# PiHAT_SSR_V4.net
KiCad netlist of a schematic drawn in EAGLE
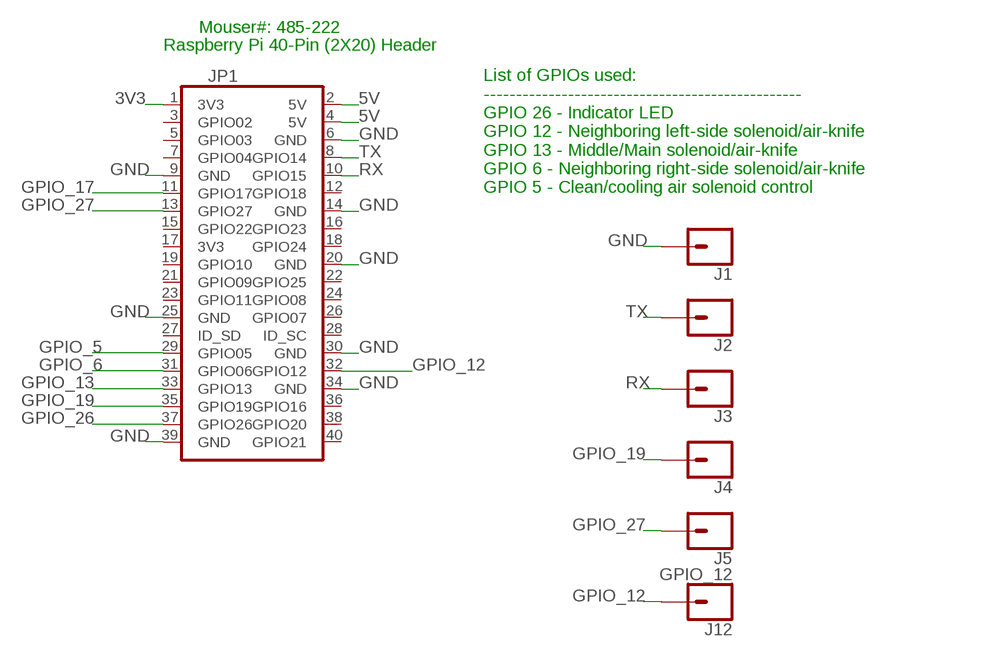
[diagram p0: schematic, sheet 1]
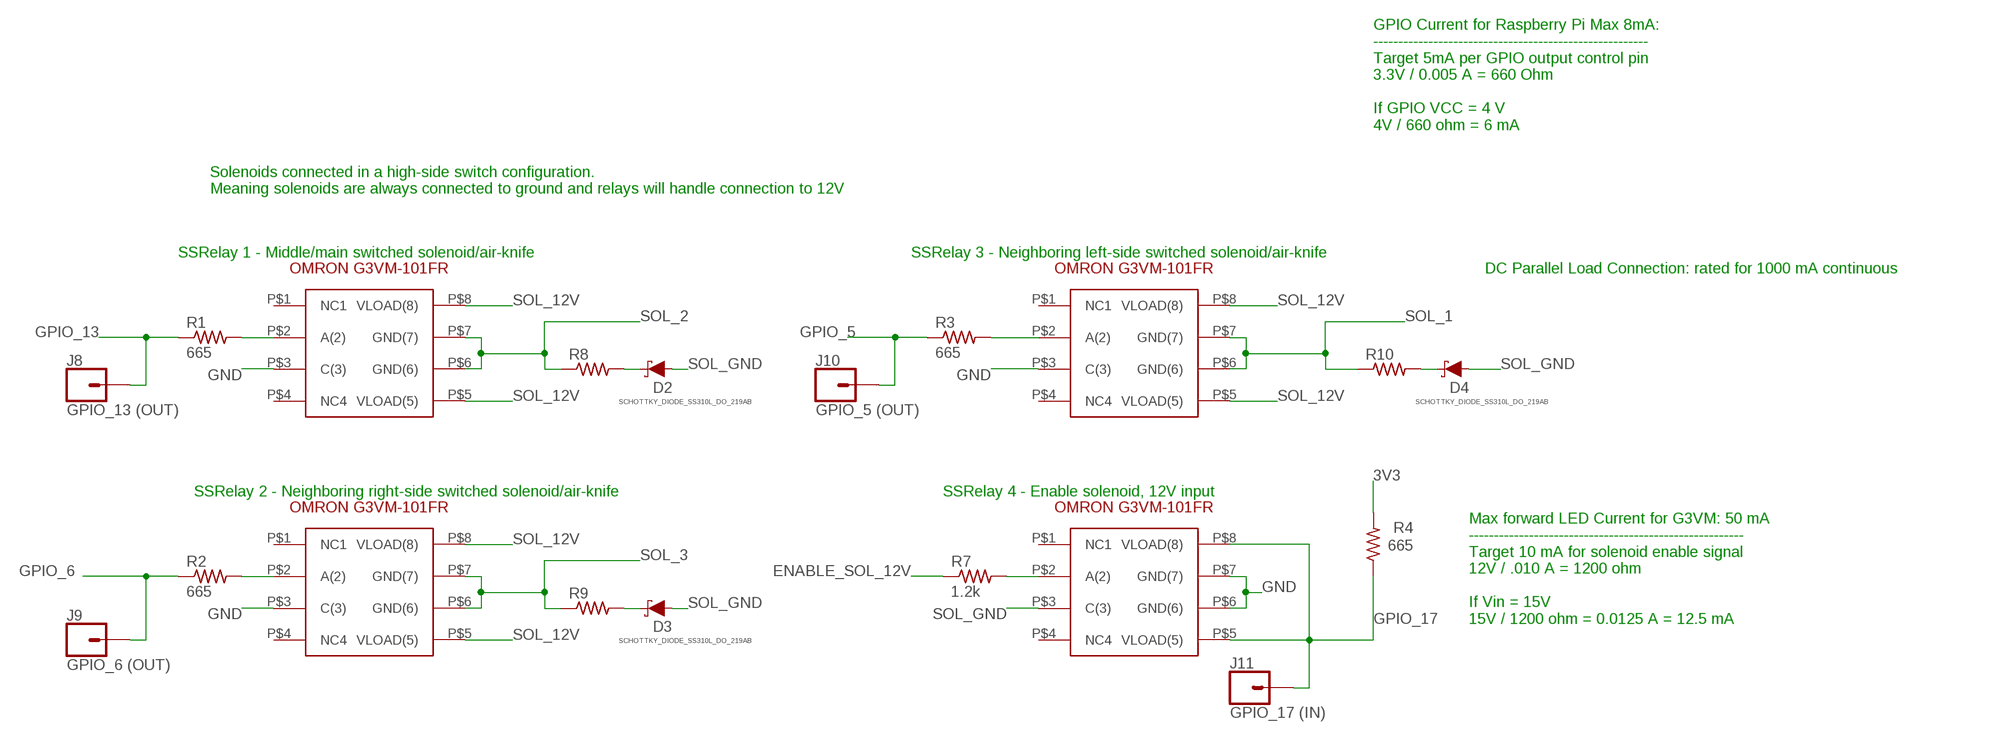
[diagram p1: schematic, sheet 2]
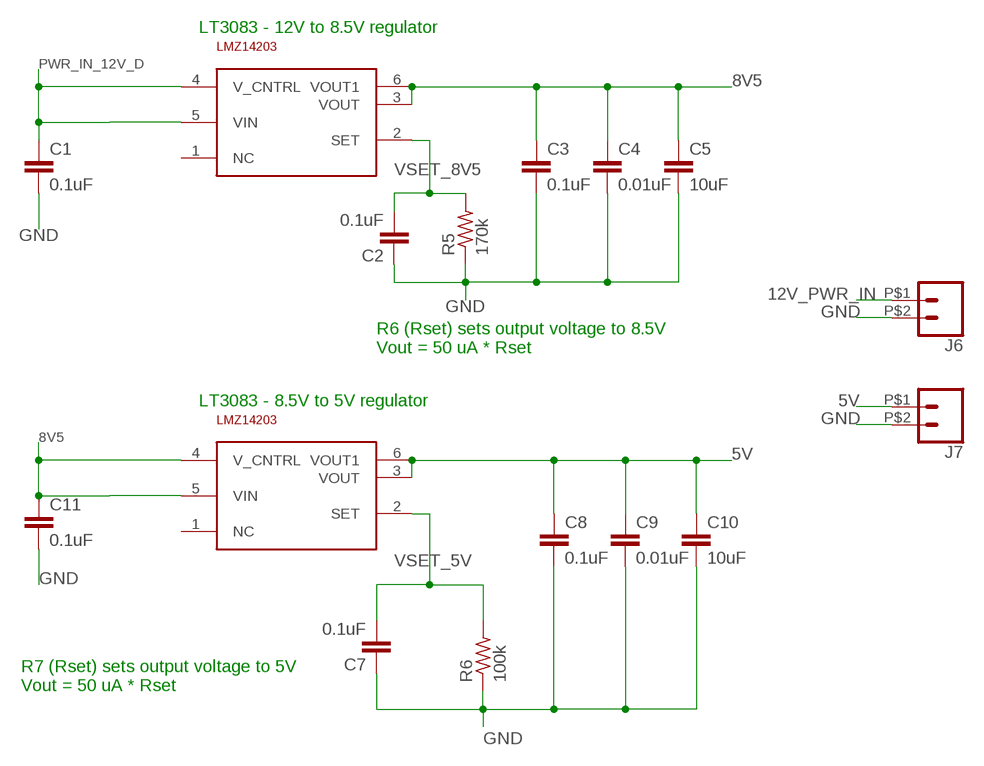
[diagram p2: schematic, sheet 3]
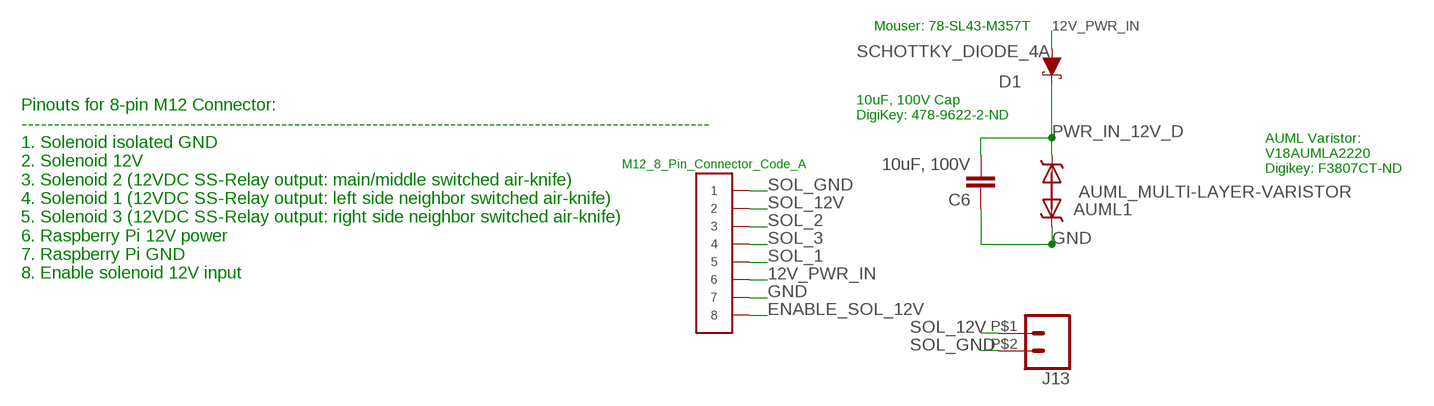
[diagram p3: schematic, sheet 4]

(export (version "E")
  (design (tool "Eeschema 10.0.6"))
  (components
    (comp (ref "AUML1")
      (value "SMD-SPECIAL_28PIN_PIC32_11_3_2011_MOD5_20_13_AUML_MULTI-LAYER-VARISTOR")
      (footprint "eagle-import:SMD-SPECIAL_28PIN_PIC32_11_3_2011_MOD5_20_13_SMT_CAP_2220")
      (libsource (lib "eagle-import") (part "SMD-SPECIAL_28PIN_PIC32_11_3_2011_MOD5_20_13_AUML_MULTI-LAYER-VARISTOR"))
    )
    (comp (ref "C6")
      (value "10uF, 100V")
      (footprint "eagle-import:C2220K")
      (libsource (lib "eagle-import") (part "C-EUC2220K"))
    )
    (comp (ref "CN1")
      (value "M12_8PIN_CODE_A")
      (footprint "eagle-import:M12_8PIN_CODE_A")
      (libsource (lib "eagle-import") (part "M12_8PIN_CODE_A"))
    )
    (comp (ref "D1")
      (value "SCHOTTKY_DIODE_4A")
      (footprint "eagle-import:SCHOTTKY_DIODE_SMD_DO-214AB")
      (libsource (lib "eagle-import") (part "SCHOTTKY_DIODE_4A"))
    )
    (comp (ref "J13")
      (value "CONN_02PTH2")
      (footprint "eagle-import:1X02_BIG")
      (libsource (lib "eagle-import") (part "CONN_02PTH2"))
    )
    (comp (ref "D2")
      (value "SCHOTTKY_DIODE_SS310L_DO_219AB")
      (footprint "eagle-import:SCHOTTKY_DIODE_DO219AB")
      (libsource (lib "eagle-import") (part "SCHOTTKY_DIODE_SS310L_DO_219AB"))
    )
    (comp (ref "D3")
      (value "SCHOTTKY_DIODE_SS310L_DO_219AB")
      (footprint "eagle-import:SCHOTTKY_DIODE_DO219AB")
      (libsource (lib "eagle-import") (part "SCHOTTKY_DIODE_SS310L_DO_219AB"))
    )
    (comp (ref "D4")
      (value "SCHOTTKY_DIODE_SS310L_DO_219AB")
      (footprint "eagle-import:SCHOTTKY_DIODE_DO219AB")
      (libsource (lib "eagle-import") (part "SCHOTTKY_DIODE_SS310L_DO_219AB"))
    )
    (comp (ref "J8")
      (value "GPIO_13 (OUT)")
      (footprint "eagle-import:1X01")
      (libsource (lib "eagle-import") (part "CONN_01"))
    )
    (comp (ref "J9")
      (value "GPIO_6 (OUT)")
      (footprint "eagle-import:1X01")
      (libsource (lib "eagle-import") (part "CONN_01"))
    )
    (comp (ref "J10")
      (value "GPIO_5 (OUT)")
      (footprint "eagle-import:1X01")
      (libsource (lib "eagle-import") (part "CONN_01"))
    )
    (comp (ref "J11")
      (value "GPIO_17 (IN)")
      (footprint "eagle-import:1X01")
      (libsource (lib "eagle-import") (part "CONN_01"))
    )
    (comp (ref "R1")
      (value "665")
      (footprint "eagle-import:M0805")
      (libsource (lib "eagle-import") (part "R-US_M0805"))
    )
    (comp (ref "R2")
      (value "665")
      (footprint "eagle-import:M0805")
      (libsource (lib "eagle-import") (part "R-US_M0805"))
    )
    (comp (ref "R3")
      (value "665")
      (footprint "eagle-import:M0805")
      (libsource (lib "eagle-import") (part "R-US_M0805"))
    )
    (comp (ref "R4")
      (value "665")
      (footprint "eagle-import:M0805")
      (libsource (lib "eagle-import") (part "R-US_M0805"))
    )
    (comp (ref "R7")
      (value "1.2k")
      (footprint "eagle-import:M0805")
      (libsource (lib "eagle-import") (part "R-US_M0805"))
    )
    (comp (ref "R8")
      (value "R-US_R2512")
      (footprint "eagle-import:R2512")
      (libsource (lib "eagle-import") (part "R-US_R2512"))
    )
    (comp (ref "R9")
      (value "R-US_R2512")
      (footprint "eagle-import:R2512")
      (libsource (lib "eagle-import") (part "R-US_R2512"))
    )
    (comp (ref "R10")
      (value "R-US_R2512")
      (footprint "eagle-import:R2512")
      (libsource (lib "eagle-import") (part "R-US_R2512"))
    )
    (comp (ref "SSR1")
      (value "OMRON_G3VM_101FR")
      (footprint "eagle-import:OMRON_G3VM-101FR")
      (libsource (lib "eagle-import") (part "OMRON_G3VM_101FR"))
    )
    (comp (ref "SSR2")
      (value "OMRON_G3VM_101FR")
      (footprint "eagle-import:OMRON_G3VM-101FR")
      (libsource (lib "eagle-import") (part "OMRON_G3VM_101FR"))
    )
    (comp (ref "SSR3")
      (value "OMRON_G3VM_101FR")
      (footprint "eagle-import:OMRON_G3VM-101FR")
      (libsource (lib "eagle-import") (part "OMRON_G3VM_101FR"))
    )
    (comp (ref "SSR4")
      (value "OMRON_G3VM_101FR")
      (footprint "eagle-import:OMRON_G3VM-101FR")
      (libsource (lib "eagle-import") (part "OMRON_G3VM_101FR"))
    )
    (comp (ref "J1")
      (value "CONN_01")
      (footprint "eagle-import:1X01")
      (libsource (lib "eagle-import") (part "CONN_01"))
    )
    (comp (ref "J2")
      (value "CONN_01")
      (footprint "eagle-import:1X01")
      (libsource (lib "eagle-import") (part "CONN_01"))
    )
    (comp (ref "J3")
      (value "CONN_01")
      (footprint "eagle-import:1X01")
      (libsource (lib "eagle-import") (part "CONN_01"))
    )
    (comp (ref "J4")
      (value "CONN_01")
      (footprint "eagle-import:1X01")
      (libsource (lib "eagle-import") (part "CONN_01"))
    )
    (comp (ref "J5")
      (value "CONN_01")
      (footprint "eagle-import:1X01")
      (libsource (lib "eagle-import") (part "CONN_01"))
    )
    (comp (ref "J12")
      (value "GPIO_12")
      (footprint "eagle-import:1X01")
      (libsource (lib "eagle-import") (part "CONN_01"))
    )
    (comp (ref "JP1")
      (value "40W_PI_HAT_TPH")
      (footprint "eagle-import:2X20")
      (libsource (lib "eagle-import") (part "40W_PI_HAT_TPH"))
    )
    (comp (ref "C1")
      (value "0.1uF")
      (footprint "eagle-import:C0805")
      (libsource (lib "eagle-import") (part "C-EUC0805"))
    )
    (comp (ref "C2")
      (value "0.1uF")
      (footprint "eagle-import:C0805")
      (libsource (lib "eagle-import") (part "C-EUC0805"))
    )
    (comp (ref "C3")
      (value "0.1uF")
      (footprint "eagle-import:C0805")
      (libsource (lib "eagle-import") (part "C-EUC0805"))
    )
    (comp (ref "C4")
      (value "0.01uF")
      (footprint "eagle-import:C0805")
      (libsource (lib "eagle-import") (part "C-EUC0805"))
    )
    (comp (ref "C5")
      (value "10uF")
      (footprint "eagle-import:C0805")
      (libsource (lib "eagle-import") (part "C-EUC0805"))
    )
    (comp (ref "C7")
      (value "0.1uF")
      (footprint "eagle-import:C0805")
      (libsource (lib "eagle-import") (part "C-EUC0805"))
    )
    (comp (ref "C8")
      (value "0.1uF")
      (footprint "eagle-import:C0805")
      (libsource (lib "eagle-import") (part "C-EUC0805"))
    )
    (comp (ref "C9")
      (value "0.01uF")
      (footprint "eagle-import:C0805")
      (libsource (lib "eagle-import") (part "C-EUC0805"))
    )
    (comp (ref "C10")
      (value "10uF")
      (footprint "eagle-import:C0805")
      (libsource (lib "eagle-import") (part "C-EUC0805"))
    )
    (comp (ref "C11")
      (value "0.1uF")
      (footprint "eagle-import:C0805")
      (libsource (lib "eagle-import") (part "C-EUC0805"))
    )
    (comp (ref "J6")
      (value "CONN_02PTH2")
      (footprint "eagle-import:1X02_BIG")
      (libsource (lib "eagle-import") (part "CONN_02PTH2"))
    )
    (comp (ref "J7")
      (value "CONN_02PTH2")
      (footprint "eagle-import:1X02_BIG")
      (libsource (lib "eagle-import") (part "CONN_02PTH2"))
    )
    (comp (ref "R5")
      (value "170k")
      (footprint "eagle-import:M0805")
      (libsource (lib "eagle-import") (part "R-US_M0805"))
    )
    (comp (ref "R6")
      (value "100k")
      (footprint "eagle-import:M0805")
      (libsource (lib "eagle-import") (part "R-US_M0805"))
    )
    (comp (ref "VR1")
      (value "SMD-SPECIAL_28PIN_PIC32_11_3_2011_LT3083")
      (footprint "eagle-import:SMD-SPECIAL_28PIN_PIC32_11_3_2011_DPAK-5")
      (libsource (lib "eagle-import") (part "SMD-SPECIAL_28PIN_PIC32_11_3_2011_LT3083"))
    )
    (comp (ref "VR2")
      (value "SMD-SPECIAL_28PIN_PIC32_11_3_2011_LT3083")
      (footprint "eagle-import:SMD-SPECIAL_28PIN_PIC32_11_3_2011_DPAK-5")
      (libsource (lib "eagle-import") (part "SMD-SPECIAL_28PIN_PIC32_11_3_2011_LT3083"))
    )
  )
  (nets
    (net (code "1") (name "3V3") (class "Default")
      (node (ref "JP1") (pin "1") (pinfunction "3V3_1") (pintype "passive"))
      (node (ref "R4") (pin "2") (pinfunction "2_2") (pintype "passive"))
    )
    (net (code "2") (name "5V") (class "Default")
      (node (ref "C10") (pin "1") (pinfunction "1_1") (pintype "passive"))
      (node (ref "C8") (pin "1") (pinfunction "1_1") (pintype "passive"))
      (node (ref "C9") (pin "1") (pinfunction "1_1") (pintype "passive"))
      (node (ref "J7") (pin "P$1") (pinfunction "1_P$1") (pintype "passive"))
      (node (ref "JP1") (pin "2") (pinfunction "5V_2") (pintype "passive"))
      (node (ref "JP1") (pin "4") (pinfunction "5V_4") (pintype "passive"))
      (node (ref "VR2") (pin "3") (pinfunction "VOUT_3") (pintype "bidirectional"))
      (node (ref "VR2") (pin "6") (pinfunction "VOUT1_6") (pintype "bidirectional"))
    )
    (net (code "3") (name "8V5") (class "Default")
      (node (ref "C11") (pin "1") (pinfunction "1_1") (pintype "passive"))
      (node (ref "C3") (pin "1") (pinfunction "1_1") (pintype "passive"))
      (node (ref "C4") (pin "1") (pinfunction "1_1") (pintype "passive"))
      (node (ref "C5") (pin "1") (pinfunction "1_1") (pintype "passive"))
      (node (ref "VR1") (pin "3") (pinfunction "VOUT_3") (pintype "bidirectional"))
      (node (ref "VR1") (pin "6") (pinfunction "VOUT1_6") (pintype "bidirectional"))
      (node (ref "VR2") (pin "4") (pinfunction "V_CNTRL_4") (pintype "bidirectional"))
      (node (ref "VR2") (pin "5") (pinfunction "VIN_5") (pintype "bidirectional"))
    )
    (net (code "4") (name "12V_PWR_IN") (class "Default")
      (node (ref "CN1") (pin "P$6") (pinfunction "P$6_P$6") (pintype "bidirectional"))
      (node (ref "D1") (pin "P$2") (pinfunction "A_P$2") (pintype "passive"))
      (node (ref "J6") (pin "P$1") (pinfunction "1_P$1") (pintype "passive"))
    )
    (net (code "5") (name "ENABLE_SOL_12V") (class "Default")
      (node (ref "CN1") (pin "P$8") (pinfunction "P$8_P$8") (pintype "bidirectional"))
      (node (ref "R7") (pin "1") (pinfunction "1_1") (pintype "passive"))
    )
    (net (code "6") (name "GND") (class "Default")
      (node (ref "AUML1") (pin "1") (pinfunction "1_1") (pintype "passive"))
      (node (ref "C1") (pin "2") (pinfunction "2_2") (pintype "passive"))
      (node (ref "C10") (pin "2") (pinfunction "2_2") (pintype "passive"))
      (node (ref "C11") (pin "2") (pinfunction "2_2") (pintype "passive"))
      (node (ref "C2") (pin "1") (pinfunction "1_1") (pintype "passive"))
      (node (ref "C3") (pin "2") (pinfunction "2_2") (pintype "passive"))
      (node (ref "C4") (pin "2") (pinfunction "2_2") (pintype "passive"))
      (node (ref "C5") (pin "2") (pinfunction "2_2") (pintype "passive"))
      (node (ref "C6") (pin "1") (pinfunction "1_1") (pintype "passive"))
      (node (ref "C7") (pin "1") (pinfunction "1_1") (pintype "passive"))
      (node (ref "C8") (pin "2") (pinfunction "2_2") (pintype "passive"))
      (node (ref "C9") (pin "2") (pinfunction "2_2") (pintype "passive"))
      (node (ref "CN1") (pin "P$7") (pinfunction "P$7_P$7") (pintype "bidirectional"))
      (node (ref "J1") (pin "1") (pinfunction "1_1") (pintype "passive"))
      (node (ref "J6") (pin "P$2") (pinfunction "2_P$2") (pintype "passive"))
      (node (ref "J7") (pin "P$2") (pinfunction "2_P$2") (pintype "passive"))
      (node (ref "JP1") (pin "14") (pinfunction "GND_14") (pintype "passive"))
      (node (ref "JP1") (pin "20") (pinfunction "GND_20") (pintype "passive"))
      (node (ref "JP1") (pin "25") (pinfunction "GND_25") (pintype "passive"))
      (node (ref "JP1") (pin "30") (pinfunction "GND_30") (pintype "passive"))
      (node (ref "JP1") (pin "34") (pinfunction "GND_34") (pintype "passive"))
      (node (ref "JP1") (pin "39") (pinfunction "GND_39") (pintype "passive"))
      (node (ref "JP1") (pin "6") (pinfunction "GND_6") (pintype "passive"))
      (node (ref "JP1") (pin "9") (pinfunction "GND_9") (pintype "passive"))
      (node (ref "R5") (pin "1") (pinfunction "1_1") (pintype "passive"))
      (node (ref "R6") (pin "1") (pinfunction "1_1") (pintype "passive"))
      (node (ref "SSR1") (pin "P$3") (pinfunction "C(3)_P$3") (pintype "bidirectional"))
      (node (ref "SSR2") (pin "P$3") (pinfunction "C(3)_P$3") (pintype "bidirectional"))
      (node (ref "SSR3") (pin "P$3") (pinfunction "C(3)_P$3") (pintype "bidirectional"))
      (node (ref "SSR4") (pin "P$6") (pinfunction "GND(6)_P$6") (pintype "bidirectional"))
      (node (ref "SSR4") (pin "P$7") (pinfunction "GND(7)_P$7") (pintype "bidirectional"))
    )
    (net (code "7") (name "GPIO_5") (class "Default")
      (node (ref "J10") (pin "1") (pinfunction "1_1") (pintype "passive"))
      (node (ref "JP1") (pin "29") (pinfunction "GPIO05_29") (pintype "passive"))
      (node (ref "R3") (pin "1") (pinfunction "1_1") (pintype "passive"))
    )
    (net (code "8") (name "GPIO_6") (class "Default")
      (node (ref "J9") (pin "1") (pinfunction "1_1") (pintype "passive"))
      (node (ref "JP1") (pin "31") (pinfunction "GPIO06_31") (pintype "passive"))
      (node (ref "R2") (pin "1") (pinfunction "1_1") (pintype "passive"))
    )
    (net (code "9") (name "GPIO_12") (class "Default")
      (node (ref "J12") (pin "1") (pinfunction "1_1") (pintype "passive"))
      (node (ref "JP1") (pin "32") (pinfunction "GPIO12_32") (pintype "passive"))
    )
    (net (code "10") (name "GPIO_13") (class "Default")
      (node (ref "J8") (pin "1") (pinfunction "1_1") (pintype "passive"))
      (node (ref "JP1") (pin "33") (pinfunction "GPIO13_33") (pintype "passive"))
      (node (ref "R1") (pin "1") (pinfunction "1_1") (pintype "passive"))
    )
    (net (code "11") (name "GPIO_17") (class "Default")
      (node (ref "J11") (pin "1") (pinfunction "1_1") (pintype "passive"))
      (node (ref "JP1") (pin "11") (pinfunction "GPIO17_11") (pintype "passive"))
      (node (ref "R4") (pin "1") (pinfunction "1_1") (pintype "passive"))
      (node (ref "SSR4") (pin "P$5") (pinfunction "VLOAD(5)_P$5") (pintype "bidirectional"))
      (node (ref "SSR4") (pin "P$8") (pinfunction "VLOAD(8)_P$8") (pintype "bidirectional"))
    )
    (net (code "12") (name "GPIO_19") (class "Default")
      (node (ref "J4") (pin "1") (pinfunction "1_1") (pintype "passive"))
      (node (ref "JP1") (pin "35") (pinfunction "GPIO19_35") (pintype "passive"))
    )
    (net (code "13") (name "GPIO_26") (class "Default")
      (node (ref "JP1") (pin "37") (pinfunction "GPIO26_37") (pintype "passive"))
    )
    (net (code "14") (name "GPIO_27") (class "Default")
      (node (ref "J5") (pin "1") (pinfunction "1_1") (pintype "passive"))
      (node (ref "JP1") (pin "13") (pinfunction "GPIO27_13") (pintype "passive"))
    )
    (net (code "15") (name "Net-(D2-C)") (class "Default")
      (node (ref "D2") (pin "P$2") (pinfunction "C_P$2") (pintype "passive"))
      (node (ref "R8") (pin "2") (pinfunction "2_2") (pintype "passive"))
    )
    (net (code "16") (name "Net-(D3-C)") (class "Default")
      (node (ref "D3") (pin "P$2") (pinfunction "C_P$2") (pintype "passive"))
      (node (ref "R9") (pin "2") (pinfunction "2_2") (pintype "passive"))
    )
    (net (code "17") (name "Net-(D4-C)") (class "Default")
      (node (ref "D4") (pin "P$2") (pinfunction "C_P$2") (pintype "passive"))
      (node (ref "R10") (pin "2") (pinfunction "2_2") (pintype "passive"))
    )
    (net (code "18") (name "Net-(SSR1-A(2))") (class "Default")
      (node (ref "R1") (pin "2") (pinfunction "2_2") (pintype "passive"))
      (node (ref "SSR1") (pin "P$2") (pinfunction "A(2)_P$2") (pintype "bidirectional"))
    )
    (net (code "19") (name "Net-(SSR2-A(2))") (class "Default")
      (node (ref "R2") (pin "2") (pinfunction "2_2") (pintype "passive"))
      (node (ref "SSR2") (pin "P$2") (pinfunction "A(2)_P$2") (pintype "bidirectional"))
    )
    (net (code "20") (name "Net-(SSR3-A(2))") (class "Default")
      (node (ref "R3") (pin "2") (pinfunction "2_2") (pintype "passive"))
      (node (ref "SSR3") (pin "P$2") (pinfunction "A(2)_P$2") (pintype "bidirectional"))
    )
    (net (code "21") (name "Net-(SSR4-A(2))") (class "Default")
      (node (ref "R7") (pin "2") (pinfunction "2_2") (pintype "passive"))
      (node (ref "SSR4") (pin "P$2") (pinfunction "A(2)_P$2") (pintype "bidirectional"))
    )
    (net (code "22") (name "PWR_IN_12V_D") (class "Default")
      (node (ref "AUML1") (pin "2") (pinfunction "2_2") (pintype "passive"))
      (node (ref "C1") (pin "1") (pinfunction "1_1") (pintype "passive"))
      (node (ref "C6") (pin "2") (pinfunction "2_2") (pintype "passive"))
      (node (ref "D1") (pin "P$1") (pinfunction "C_P$1") (pintype "passive"))
      (node (ref "VR1") (pin "4") (pinfunction "V_CNTRL_4") (pintype "bidirectional"))
      (node (ref "VR1") (pin "5") (pinfunction "VIN_5") (pintype "bidirectional"))
    )
    (net (code "23") (name "RX") (class "Default")
      (node (ref "J3") (pin "1") (pinfunction "1_1") (pintype "passive"))
      (node (ref "JP1") (pin "10") (pinfunction "GPIO15_10") (pintype "passive"))
    )
    (net (code "24") (name "SOL_1") (class "Default")
      (node (ref "CN1") (pin "P$5") (pinfunction "P$5_P$5") (pintype "bidirectional"))
      (node (ref "R10") (pin "1") (pinfunction "1_1") (pintype "passive"))
      (node (ref "SSR3") (pin "P$6") (pinfunction "GND(6)_P$6") (pintype "bidirectional"))
      (node (ref "SSR3") (pin "P$7") (pinfunction "GND(7)_P$7") (pintype "bidirectional"))
    )
    (net (code "25") (name "SOL_2") (class "Default")
      (node (ref "CN1") (pin "P$3") (pinfunction "P$3_P$3") (pintype "bidirectional"))
      (node (ref "R8") (pin "1") (pinfunction "1_1") (pintype "passive"))
      (node (ref "SSR1") (pin "P$6") (pinfunction "GND(6)_P$6") (pintype "bidirectional"))
      (node (ref "SSR1") (pin "P$7") (pinfunction "GND(7)_P$7") (pintype "bidirectional"))
    )
    (net (code "26") (name "SOL_3") (class "Default")
      (node (ref "CN1") (pin "P$4") (pinfunction "P$4_P$4") (pintype "bidirectional"))
      (node (ref "R9") (pin "1") (pinfunction "1_1") (pintype "passive"))
      (node (ref "SSR2") (pin "P$6") (pinfunction "GND(6)_P$6") (pintype "bidirectional"))
      (node (ref "SSR2") (pin "P$7") (pinfunction "GND(7)_P$7") (pintype "bidirectional"))
    )
    (net (code "27") (name "SOL_12V") (class "Default")
      (node (ref "CN1") (pin "P$2") (pinfunction "P$2_P$2") (pintype "bidirectional"))
      (node (ref "J13") (pin "P$1") (pinfunction "1_P$1") (pintype "passive"))
      (node (ref "SSR1") (pin "P$5") (pinfunction "VLOAD(5)_P$5") (pintype "bidirectional"))
      (node (ref "SSR1") (pin "P$8") (pinfunction "VLOAD(8)_P$8") (pintype "bidirectional"))
      (node (ref "SSR2") (pin "P$5") (pinfunction "VLOAD(5)_P$5") (pintype "bidirectional"))
      (node (ref "SSR2") (pin "P$8") (pinfunction "VLOAD(8)_P$8") (pintype "bidirectional"))
      (node (ref "SSR3") (pin "P$5") (pinfunction "VLOAD(5)_P$5") (pintype "bidirectional"))
      (node (ref "SSR3") (pin "P$8") (pinfunction "VLOAD(8)_P$8") (pintype "bidirectional"))
    )
    (net (code "28") (name "SOL_GND") (class "Default")
      (node (ref "CN1") (pin "P$1") (pinfunction "P$1_P$1") (pintype "bidirectional"))
      (node (ref "D2") (pin "P$1") (pinfunction "A_P$1") (pintype "passive"))
      (node (ref "D3") (pin "P$1") (pinfunction "A_P$1") (pintype "passive"))
      (node (ref "D4") (pin "P$1") (pinfunction "A_P$1") (pintype "passive"))
      (node (ref "J13") (pin "P$2") (pinfunction "2_P$2") (pintype "passive"))
      (node (ref "SSR4") (pin "P$3") (pinfunction "C(3)_P$3") (pintype "bidirectional"))
    )
    (net (code "29") (name "TX") (class "Default")
      (node (ref "J2") (pin "1") (pinfunction "1_1") (pintype "passive"))
      (node (ref "JP1") (pin "8") (pinfunction "GPIO14_8") (pintype "passive"))
    )
    (net (code "30") (name "VSET_5V") (class "Default")
      (node (ref "C7") (pin "2") (pinfunction "2_2") (pintype "passive"))
      (node (ref "R6") (pin "2") (pinfunction "2_2") (pintype "passive"))
      (node (ref "VR2") (pin "2") (pinfunction "SET_2") (pintype "bidirectional"))
    )
    (net (code "31") (name "VSET_8V5") (class "Default")
      (node (ref "C2") (pin "2") (pinfunction "2_2") (pintype "passive"))
      (node (ref "R5") (pin "2") (pinfunction "2_2") (pintype "passive"))
      (node (ref "VR1") (pin "2") (pinfunction "SET_2") (pintype "bidirectional"))
    )
    (net (code "32") (name "unconnected-(JP1-3V3-Pad17)") (class "Default")
      (node (ref "JP1") (pin "17") (pinfunction "3V3_17") (pintype "passive"))
    )
    (net (code "33") (name "unconnected-(JP1-GPIO02-Pad3)") (class "Default")
      (node (ref "JP1") (pin "3") (pinfunction "GPIO02_3") (pintype "passive"))
    )
    (net (code "34") (name "unconnected-(JP1-GPIO03-Pad5)") (class "Default")
      (node (ref "JP1") (pin "5") (pinfunction "GPIO03_5") (pintype "passive"))
    )
    (net (code "35") (name "unconnected-(JP1-GPIO04-Pad7)") (class "Default")
      (node (ref "JP1") (pin "7") (pinfunction "GPIO04_7") (pintype "passive"))
    )
    (net (code "36") (name "unconnected-(JP1-GPIO07-Pad26)") (class "Default")
      (node (ref "JP1") (pin "26") (pinfunction "GPIO07_26") (pintype "passive"))
    )
    (net (code "37") (name "unconnected-(JP1-GPIO08-Pad24)") (class "Default")
      (node (ref "JP1") (pin "24") (pinfunction "GPIO08_24") (pintype "passive"))
    )
    (net (code "38") (name "unconnected-(JP1-GPIO09-Pad21)") (class "Default")
      (node (ref "JP1") (pin "21") (pinfunction "GPIO09_21") (pintype "passive"))
    )
    (net (code "39") (name "unconnected-(JP1-GPIO10-Pad19)") (class "Default")
      (node (ref "JP1") (pin "19") (pinfunction "GPIO10_19") (pintype "passive"))
    )
    (net (code "40") (name "unconnected-(JP1-GPIO11-Pad23)") (class "Default")
      (node (ref "JP1") (pin "23") (pinfunction "GPIO11_23") (pintype "passive"))
    )
    (net (code "41") (name "unconnected-(JP1-GPIO16-Pad36)") (class "Default")
      (node (ref "JP1") (pin "36") (pinfunction "GPIO16_36") (pintype "passive"))
    )
    (net (code "42") (name "unconnected-(JP1-GPIO18-Pad12)") (class "Default")
      (node (ref "JP1") (pin "12") (pinfunction "GPIO18_12") (pintype "passive"))
    )
    (net (code "43") (name "unconnected-(JP1-GPIO20-Pad38)") (class "Default")
      (node (ref "JP1") (pin "38") (pinfunction "GPIO20_38") (pintype "passive"))
    )
    (net (code "44") (name "unconnected-(JP1-GPIO21-Pad40)") (class "Default")
      (node (ref "JP1") (pin "40") (pinfunction "GPIO21_40") (pintype "passive"))
    )
    (net (code "45") (name "unconnected-(JP1-GPIO22-Pad15)") (class "Default")
      (node (ref "JP1") (pin "15") (pinfunction "GPIO22_15") (pintype "passive"))
    )
    (net (code "46") (name "unconnected-(JP1-GPIO23-Pad16)") (class "Default")
      (node (ref "JP1") (pin "16") (pinfunction "GPIO23_16") (pintype "passive"))
    )
    (net (code "47") (name "unconnected-(JP1-GPIO24-Pad18)") (class "Default")
      (node (ref "JP1") (pin "18") (pinfunction "GPIO24_18") (pintype "passive"))
    )
    (net (code "48") (name "unconnected-(JP1-GPIO25-Pad22)") (class "Default")
      (node (ref "JP1") (pin "22") (pinfunction "GPIO25_22") (pintype "passive"))
    )
    (net (code "49") (name "unconnected-(JP1-ID_SC-Pad28)") (class "Default")
      (node (ref "JP1") (pin "28") (pinfunction "ID_SC_28") (pintype "passive"))
    )
    (net (code "50") (name "unconnected-(JP1-ID_SD-Pad27)") (class "Default")
      (node (ref "JP1") (pin "27") (pinfunction "ID_SD_27") (pintype "passive"))
    )
    (net (code "51") (name "unconnected-(SSR1-NC1-PadP$1)") (class "Default")
      (node (ref "SSR1") (pin "P$1") (pinfunction "NC1_P$1") (pintype "bidirectional"))
    )
    (net (code "52") (name "unconnected-(SSR1-NC4-PadP$4)") (class "Default")
      (node (ref "SSR1") (pin "P$4") (pinfunction "NC4_P$4") (pintype "bidirectional"))
    )
    (net (code "53") (name "unconnected-(SSR2-NC1-PadP$1)") (class "Default")
      (node (ref "SSR2") (pin "P$1") (pinfunction "NC1_P$1") (pintype "bidirectional"))
    )
    (net (code "54") (name "unconnected-(SSR2-NC4-PadP$4)") (class "Default")
      (node (ref "SSR2") (pin "P$4") (pinfunction "NC4_P$4") (pintype "bidirectional"))
    )
    (net (code "55") (name "unconnected-(SSR3-NC1-PadP$1)") (class "Default")
      (node (ref "SSR3") (pin "P$1") (pinfunction "NC1_P$1") (pintype "bidirectional"))
    )
    (net (code "56") (name "unconnected-(SSR3-NC4-PadP$4)") (class "Default")
      (node (ref "SSR3") (pin "P$4") (pinfunction "NC4_P$4") (pintype "bidirectional"))
    )
    (net (code "57") (name "unconnected-(SSR4-NC1-PadP$1)") (class "Default")
      (node (ref "SSR4") (pin "P$1") (pinfunction "NC1_P$1") (pintype "bidirectional"))
    )
    (net (code "58") (name "unconnected-(SSR4-NC4-PadP$4)") (class "Default")
      (node (ref "SSR4") (pin "P$4") (pinfunction "NC4_P$4") (pintype "bidirectional"))
    )
    (net (code "59") (name "unconnected-(VR1-NC-Pad1)") (class "Default")
      (node (ref "VR1") (pin "1") (pinfunction "NC_1") (pintype "bidirectional"))
    )
    (net (code "60") (name "unconnected-(VR2-NC-Pad1)") (class "Default")
      (node (ref "VR2") (pin "1") (pinfunction "NC_1") (pintype "bidirectional"))
    )
  )
)
